# LcsNodes-Building-Block-Extension-Logic.net
KiCad netlist of a schematic drawn in EasyEDA
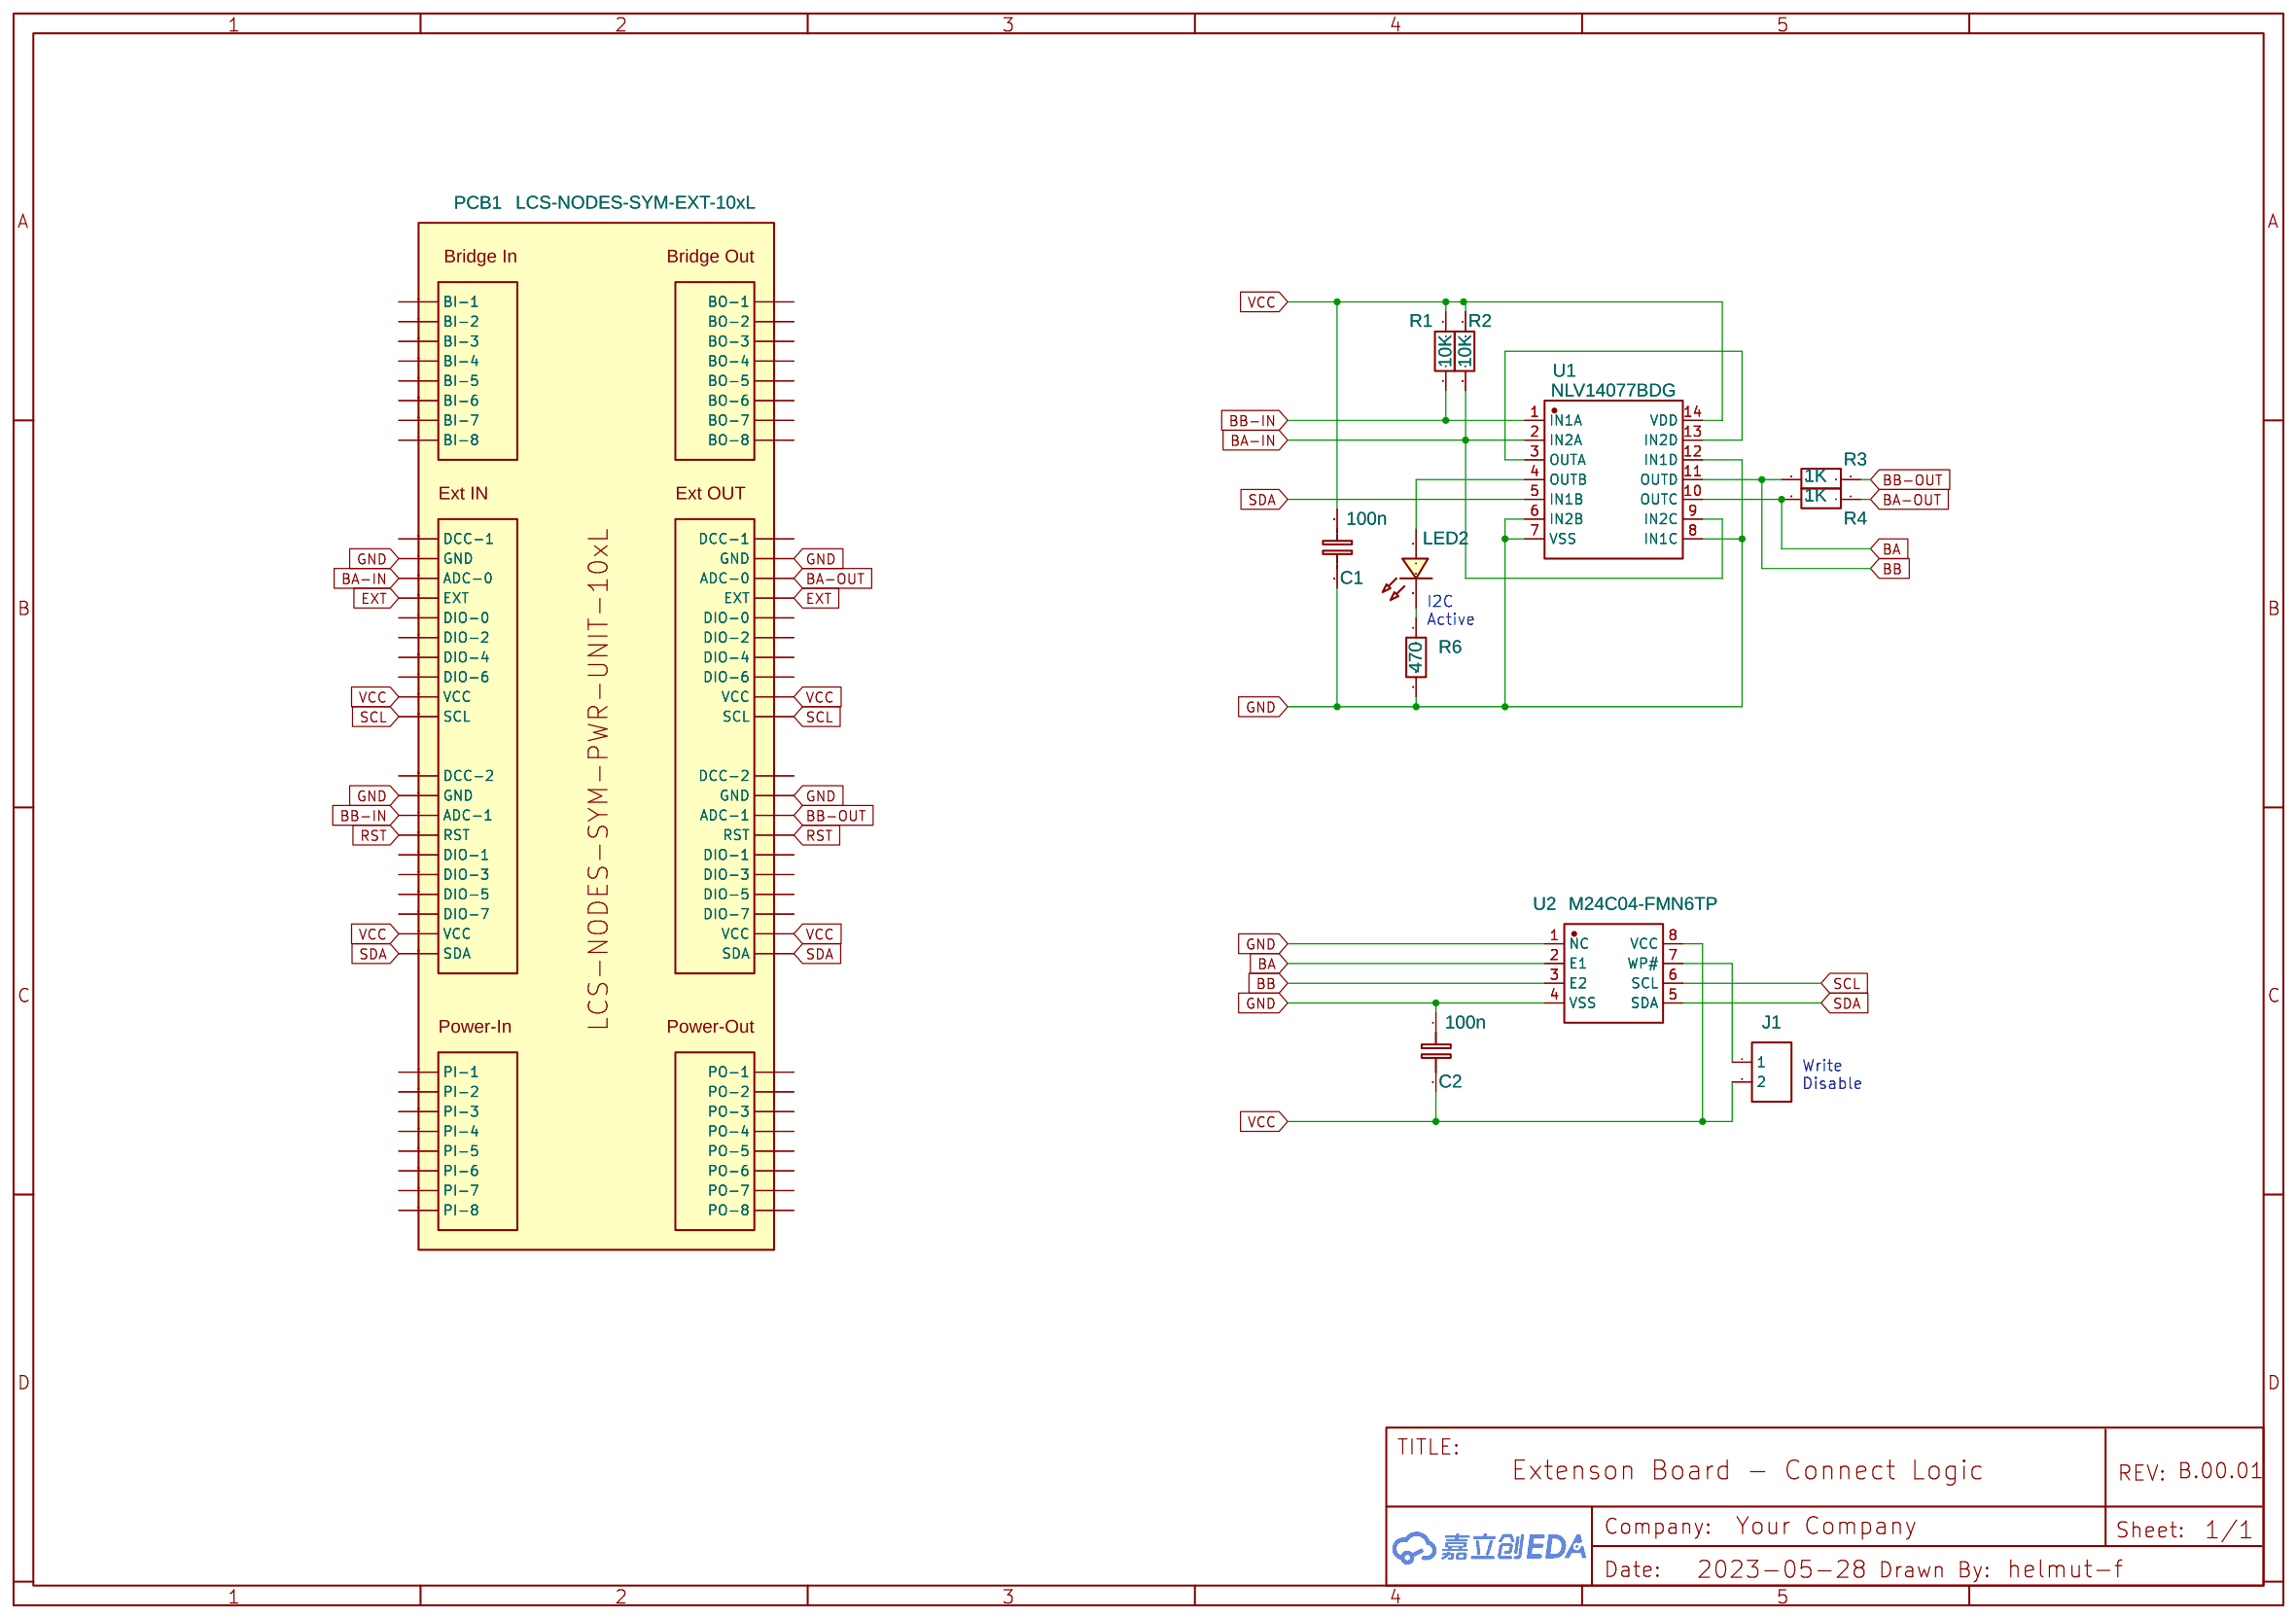
[diagram p0: schematic sheet]

(export (version "E")
  (design (tool "Eeschema 10.0.6"))
  (components
    (comp (ref "C1") (value "100n") (libsource (lib "") (part "C_0603_EU_1")))
    (comp (ref "C2") (value "100n") (libsource (lib "") (part "C_0603_EU")))
    (comp (ref "J1") (value "HDR-M-2.54_1x2") (libsource (lib "") (part "HDR-M-2.54_1x2")))
    (comp (ref "LED2")
      (value "LED-0805_G")
      (fields (field (name "Manufacturer Part") "NCD0805G1") (field (name "Manufacturer") "国星光电"))
      (libsource (lib "") (part "LED-0805_G"))
    )
    (comp (ref "PCB1") (value "LCS-NODES-SYM-EXT-10xL") (libsource (lib "") (part "LCS-NODES-SYM-EXT-10X8")))
    (comp (ref "R1") (value "10K") (libsource (lib "") (part "R_AXIAL-0.3_EU")))
    (comp (ref "R2") (value "10K") (libsource (lib "") (part "R_AXIAL-0.3_EU")))
    (comp (ref "R3") (value "1K") (libsource (lib "") (part "R_AXIAL-0.3_EU_1")))
    (comp (ref "R4") (value "1K") (libsource (lib "") (part "R_AXIAL-0.3_EU_1")))
    (comp (ref "R6") (value "470") (libsource (lib "") (part "R_0805_EU")))
    (comp (ref "U1")
      (value "NLV14077BDG")
      (fields (field (name "Manufacturer") "onsemi(安森美)"))
      (libsource (lib "") (part "NLV14077BDG"))
    )
    (comp (ref "U2")
      (value "M24C04-FMN6TP")
      (fields (field (name "Manufacturer") "ST(意法半导体)"))
      (libsource (lib "") (part "M24C04-FMN6TP"))
    )
  )
  (nets
    (net (code "1") (name "BA") (class "Default")
      (node (ref "R4") (pin "2") (pinfunction "2_2") (pintype "unspecified"))
      (node (ref "U1") (pin "10") (pinfunction "OUTC_10") (pintype "unspecified"))
      (node (ref "U2") (pin "2") (pinfunction "E1_2") (pintype "unspecified"))
    )
    (net (code "2") (name "BA-IN") (class "Default")
      (node (ref "PCB1") (pin "22") (pinfunction "ADC-0_22") (pintype "unspecified"))
      (node (ref "R2") (pin "2") (pinfunction "2_2") (pintype "unspecified"))
      (node (ref "U1") (pin "2") (pinfunction "IN2A_2") (pintype "unspecified"))
      (node (ref "U1") (pin "9") (pinfunction "IN2C_9") (pintype "unspecified"))
    )
    (net (code "3") (name "BA-OUT") (class "Default")
      (node (ref "PCB1") (pin "62") (pinfunction "ADC-0_62") (pintype "unspecified"))
      (node (ref "R4") (pin "1") (pinfunction "1_1") (pintype "unspecified"))
    )
    (net (code "4") (name "BB") (class "Default")
      (node (ref "R3") (pin "2") (pinfunction "2_2") (pintype "unspecified"))
      (node (ref "U1") (pin "11") (pinfunction "OUTD_11") (pintype "unspecified"))
      (node (ref "U2") (pin "3") (pinfunction "E2_3") (pintype "unspecified"))
    )
    (net (code "5") (name "BB-IN") (class "Default")
      (node (ref "PCB1") (pin "32") (pinfunction "ADC-1_32") (pintype "unspecified"))
      (node (ref "R1") (pin "2") (pinfunction "2_2") (pintype "unspecified"))
      (node (ref "U1") (pin "1") (pinfunction "IN1A_1") (pintype "unspecified"))
    )
    (net (code "6") (name "BB-OUT") (class "Default")
      (node (ref "PCB1") (pin "72") (pinfunction "ADC-1_72") (pintype "unspecified"))
      (node (ref "R3") (pin "1") (pinfunction "1_1") (pintype "unspecified"))
    )
    (net (code "7") (name "EXT") (class "Default")
      (node (ref "PCB1") (pin "23") (pinfunction "EXT_23") (pintype "unspecified"))
      (node (ref "PCB1") (pin "63") (pinfunction "EXT_63") (pintype "unspecified"))
    )
    (net (code "8") (name "GND") (class "Default")
      (node (ref "C1") (pin "2") (pinfunction "2_2") (pintype "unspecified"))
      (node (ref "C2") (pin "1") (pinfunction "1_1") (pintype "unspecified"))
      (node (ref "PCB1") (pin "21") (pinfunction "GND_21") (pintype "unspecified"))
      (node (ref "PCB1") (pin "31") (pinfunction "GND_31") (pintype "unspecified"))
      (node (ref "PCB1") (pin "61") (pinfunction "GND_61") (pintype "unspecified"))
      (node (ref "PCB1") (pin "71") (pinfunction "GND_71") (pintype "unspecified"))
      (node (ref "R6") (pin "2") (pinfunction "2_2") (pintype "unspecified"))
      (node (ref "U1") (pin "12") (pinfunction "IN1D_12") (pintype "unspecified"))
      (node (ref "U1") (pin "6") (pinfunction "IN2B_6") (pintype "unspecified"))
      (node (ref "U1") (pin "7") (pinfunction "VSS_7") (pintype "unspecified"))
      (node (ref "U1") (pin "8") (pinfunction "IN1C_8") (pintype "unspecified"))
      (node (ref "U2") (pin "1") (pinfunction "NC_1") (pintype "unspecified"))
      (node (ref "U2") (pin "4") (pinfunction "VSS_4") (pintype "unspecified"))
    )
    (net (code "9") (name "Net-(LED2-Pad2)") (class "Default")
      (node (ref "LED2") (pin "2") (pinfunction "2_2") (pintype "unspecified"))
      (node (ref "R6") (pin "1") (pinfunction "1_1") (pintype "unspecified"))
    )
    (net (code "10") (name "Net-(U1-IN2D)") (class "Default")
      (node (ref "U1") (pin "13") (pinfunction "IN2D_13") (pintype "unspecified"))
      (node (ref "U1") (pin "3") (pinfunction "OUTA_3") (pintype "unspecified"))
    )
    (net (code "11") (name "Net-(U1-OUTB)") (class "Default")
      (node (ref "LED2") (pin "1") (pinfunction "1_1") (pintype "unspecified"))
      (node (ref "U1") (pin "4") (pinfunction "OUTB_4") (pintype "unspecified"))
    )
    (net (code "12") (name "Net-(U2-WP#)") (class "Default")
      (node (ref "J1") (pin "1") (pinfunction "1_1") (pintype "unspecified"))
      (node (ref "U2") (pin "7") (pinfunction "WP#_7") (pintype "unspecified"))
    )
    (net (code "13") (name "RST") (class "Default")
      (node (ref "PCB1") (pin "33") (pinfunction "RST_33") (pintype "unspecified"))
      (node (ref "PCB1") (pin "73") (pinfunction "RST_73") (pintype "unspecified"))
    )
    (net (code "14") (name "SCL") (class "Default")
      (node (ref "PCB1") (pin "29") (pinfunction "SCL_29") (pintype "unspecified"))
      (node (ref "PCB1") (pin "69") (pinfunction "SCL_69") (pintype "unspecified"))
      (node (ref "U2") (pin "6") (pinfunction "SCL_6") (pintype "unspecified"))
    )
    (net (code "15") (name "SDA") (class "Default")
      (node (ref "PCB1") (pin "39") (pinfunction "SDA_39") (pintype "unspecified"))
      (node (ref "PCB1") (pin "79") (pinfunction "SDA_79") (pintype "unspecified"))
      (node (ref "U1") (pin "5") (pinfunction "IN1B_5") (pintype "unspecified"))
      (node (ref "U2") (pin "5") (pinfunction "SDA_5") (pintype "unspecified"))
    )
    (net (code "16") (name "VCC") (class "Default")
      (node (ref "C1") (pin "1") (pinfunction "1_1") (pintype "unspecified"))
      (node (ref "C2") (pin "2") (pinfunction "2_2") (pintype "unspecified"))
      (node (ref "J1") (pin "2") (pinfunction "2_2") (pintype "unspecified"))
      (node (ref "PCB1") (pin "28") (pinfunction "VCC_28") (pintype "unspecified"))
      (node (ref "PCB1") (pin "38") (pinfunction "VCC_38") (pintype "unspecified"))
      (node (ref "PCB1") (pin "68") (pinfunction "VCC_68") (pintype "unspecified"))
      (node (ref "PCB1") (pin "78") (pinfunction "VCC_78") (pintype "unspecified"))
      (node (ref "R1") (pin "1") (pinfunction "1_1") (pintype "unspecified"))
      (node (ref "R2") (pin "1") (pinfunction "1_1") (pintype "unspecified"))
      (node (ref "U1") (pin "14") (pinfunction "VDD_14") (pintype "unspecified"))
      (node (ref "U2") (pin "8") (pinfunction "VCC_8") (pintype "unspecified"))
    )
    (net (code "17") (name "unconnected-(PCB1-BI-1-Pad10)") (class "Default")
      (node (ref "PCB1") (pin "10") (pinfunction "BI-1_10") (pintype "unspecified"))
    )
    (net (code "18") (name "unconnected-(PCB1-BI-2-Pad11)") (class "Default")
      (node (ref "PCB1") (pin "11") (pinfunction "BI-2_11") (pintype "unspecified"))
    )
    (net (code "19") (name "unconnected-(PCB1-BI-3-Pad12)") (class "Default")
      (node (ref "PCB1") (pin "12") (pinfunction "BI-3_12") (pintype "unspecified"))
    )
    (net (code "20") (name "unconnected-(PCB1-BI-4-Pad13)") (class "Default")
      (node (ref "PCB1") (pin "13") (pinfunction "BI-4_13") (pintype "unspecified"))
    )
    (net (code "21") (name "unconnected-(PCB1-BI-5-Pad14)") (class "Default")
      (node (ref "PCB1") (pin "14") (pinfunction "BI-5_14") (pintype "unspecified"))
    )
    (net (code "22") (name "unconnected-(PCB1-BI-6-Pad15)") (class "Default")
      (node (ref "PCB1") (pin "15") (pinfunction "BI-6_15") (pintype "unspecified"))
    )
    (net (code "23") (name "unconnected-(PCB1-BI-7-Pad16)") (class "Default")
      (node (ref "PCB1") (pin "16") (pinfunction "BI-7_16") (pintype "unspecified"))
    )
    (net (code "24") (name "unconnected-(PCB1-BI-8-Pad17)") (class "Default")
      (node (ref "PCB1") (pin "17") (pinfunction "BI-8_17") (pintype "unspecified"))
    )
    (net (code "25") (name "unconnected-(PCB1-BO-1-Pad50)") (class "Default")
      (node (ref "PCB1") (pin "50") (pinfunction "BO-1_50") (pintype "unspecified"))
    )
    (net (code "26") (name "unconnected-(PCB1-BO-2-Pad51)") (class "Default")
      (node (ref "PCB1") (pin "51") (pinfunction "BO-2_51") (pintype "unspecified"))
    )
    (net (code "27") (name "unconnected-(PCB1-BO-3-Pad52)") (class "Default")
      (node (ref "PCB1") (pin "52") (pinfunction "BO-3_52") (pintype "unspecified"))
    )
    (net (code "28") (name "unconnected-(PCB1-BO-4-Pad53)") (class "Default")
      (node (ref "PCB1") (pin "53") (pinfunction "BO-4_53") (pintype "unspecified"))
    )
    (net (code "29") (name "unconnected-(PCB1-BO-5-Pad54)") (class "Default")
      (node (ref "PCB1") (pin "54") (pinfunction "BO-5_54") (pintype "unspecified"))
    )
    (net (code "30") (name "unconnected-(PCB1-BO-6-Pad55)") (class "Default")
      (node (ref "PCB1") (pin "55") (pinfunction "BO-6_55") (pintype "unspecified"))
    )
    (net (code "31") (name "unconnected-(PCB1-BO-7-Pad56)") (class "Default")
      (node (ref "PCB1") (pin "56") (pinfunction "BO-7_56") (pintype "unspecified"))
    )
    (net (code "32") (name "unconnected-(PCB1-BO-8-Pad57)") (class "Default")
      (node (ref "PCB1") (pin "57") (pinfunction "BO-8_57") (pintype "unspecified"))
    )
    (net (code "33") (name "unconnected-(PCB1-DCC-1-Pad20)") (class "Default")
      (node (ref "PCB1") (pin "20") (pinfunction "DCC-1_20") (pintype "unspecified"))
    )
    (net (code "34") (name "unconnected-(PCB1-DCC-1-Pad60)") (class "Default")
      (node (ref "PCB1") (pin "60") (pinfunction "DCC-1_60") (pintype "unspecified"))
    )
    (net (code "35") (name "unconnected-(PCB1-DCC-2-Pad30)") (class "Default")
      (node (ref "PCB1") (pin "30") (pinfunction "DCC-2_30") (pintype "unspecified"))
    )
    (net (code "36") (name "unconnected-(PCB1-DCC-2-Pad70)") (class "Default")
      (node (ref "PCB1") (pin "70") (pinfunction "DCC-2_70") (pintype "unspecified"))
    )
    (net (code "37") (name "unconnected-(PCB1-DIO-0-Pad24)") (class "Default")
      (node (ref "PCB1") (pin "24") (pinfunction "DIO-0_24") (pintype "unspecified"))
    )
    (net (code "38") (name "unconnected-(PCB1-DIO-0-Pad64)") (class "Default")
      (node (ref "PCB1") (pin "64") (pinfunction "DIO-0_64") (pintype "unspecified"))
    )
    (net (code "39") (name "unconnected-(PCB1-DIO-1-Pad34)") (class "Default")
      (node (ref "PCB1") (pin "34") (pinfunction "DIO-1_34") (pintype "unspecified"))
    )
    (net (code "40") (name "unconnected-(PCB1-DIO-1-Pad74)") (class "Default")
      (node (ref "PCB1") (pin "74") (pinfunction "DIO-1_74") (pintype "unspecified"))
    )
    (net (code "41") (name "unconnected-(PCB1-DIO-2-Pad25)") (class "Default")
      (node (ref "PCB1") (pin "25") (pinfunction "DIO-2_25") (pintype "unspecified"))
    )
    (net (code "42") (name "unconnected-(PCB1-DIO-2-Pad65)") (class "Default")
      (node (ref "PCB1") (pin "65") (pinfunction "DIO-2_65") (pintype "unspecified"))
    )
    (net (code "43") (name "unconnected-(PCB1-DIO-3-Pad35)") (class "Default")
      (node (ref "PCB1") (pin "35") (pinfunction "DIO-3_35") (pintype "unspecified"))
    )
    (net (code "44") (name "unconnected-(PCB1-DIO-3-Pad75)") (class "Default")
      (node (ref "PCB1") (pin "75") (pinfunction "DIO-3_75") (pintype "unspecified"))
    )
    (net (code "45") (name "unconnected-(PCB1-DIO-4-Pad26)") (class "Default")
      (node (ref "PCB1") (pin "26") (pinfunction "DIO-4_26") (pintype "unspecified"))
    )
    (net (code "46") (name "unconnected-(PCB1-DIO-4-Pad66)") (class "Default")
      (node (ref "PCB1") (pin "66") (pinfunction "DIO-4_66") (pintype "unspecified"))
    )
    (net (code "47") (name "unconnected-(PCB1-DIO-5-Pad36)") (class "Default")
      (node (ref "PCB1") (pin "36") (pinfunction "DIO-5_36") (pintype "unspecified"))
    )
    (net (code "48") (name "unconnected-(PCB1-DIO-5-Pad76)") (class "Default")
      (node (ref "PCB1") (pin "76") (pinfunction "DIO-5_76") (pintype "unspecified"))
    )
    (net (code "49") (name "unconnected-(PCB1-DIO-6-Pad27)") (class "Default")
      (node (ref "PCB1") (pin "27") (pinfunction "DIO-6_27") (pintype "unspecified"))
    )
    (net (code "50") (name "unconnected-(PCB1-DIO-6-Pad67)") (class "Default")
      (node (ref "PCB1") (pin "67") (pinfunction "DIO-6_67") (pintype "unspecified"))
    )
    (net (code "51") (name "unconnected-(PCB1-DIO-7-Pad37)") (class "Default")
      (node (ref "PCB1") (pin "37") (pinfunction "DIO-7_37") (pintype "unspecified"))
    )
    (net (code "52") (name "unconnected-(PCB1-DIO-7-Pad77)") (class "Default")
      (node (ref "PCB1") (pin "77") (pinfunction "DIO-7_77") (pintype "unspecified"))
    )
    (net (code "53") (name "unconnected-(PCB1-PI-1-Pad40)") (class "Default")
      (node (ref "PCB1") (pin "40") (pinfunction "PI-1_40") (pintype "unspecified"))
    )
    (net (code "54") (name "unconnected-(PCB1-PI-2-Pad41)") (class "Default")
      (node (ref "PCB1") (pin "41") (pinfunction "PI-2_41") (pintype "unspecified"))
    )
    (net (code "55") (name "unconnected-(PCB1-PI-3-Pad42)") (class "Default")
      (node (ref "PCB1") (pin "42") (pinfunction "PI-3_42") (pintype "unspecified"))
    )
    (net (code "56") (name "unconnected-(PCB1-PI-4-Pad43)") (class "Default")
      (node (ref "PCB1") (pin "43") (pinfunction "PI-4_43") (pintype "unspecified"))
    )
    (net (code "57") (name "unconnected-(PCB1-PI-5-Pad44)") (class "Default")
      (node (ref "PCB1") (pin "44") (pinfunction "PI-5_44") (pintype "unspecified"))
    )
    (net (code "58") (name "unconnected-(PCB1-PI-6-Pad45)") (class "Default")
      (node (ref "PCB1") (pin "45") (pinfunction "PI-6_45") (pintype "unspecified"))
    )
    (net (code "59") (name "unconnected-(PCB1-PI-7-Pad46)") (class "Default")
      (node (ref "PCB1") (pin "46") (pinfunction "PI-7_46") (pintype "unspecified"))
    )
    (net (code "60") (name "unconnected-(PCB1-PI-8-Pad47)") (class "Default")
      (node (ref "PCB1") (pin "47") (pinfunction "PI-8_47") (pintype "unspecified"))
    )
    (net (code "61") (name "unconnected-(PCB1-PO-1-Pad80)") (class "Default")
      (node (ref "PCB1") (pin "80") (pinfunction "PO-1_80") (pintype "unspecified"))
    )
    (net (code "62") (name "unconnected-(PCB1-PO-2-Pad81)") (class "Default")
      (node (ref "PCB1") (pin "81") (pinfunction "PO-2_81") (pintype "unspecified"))
    )
    (net (code "63") (name "unconnected-(PCB1-PO-3-Pad82)") (class "Default")
      (node (ref "PCB1") (pin "82") (pinfunction "PO-3_82") (pintype "unspecified"))
    )
    (net (code "64") (name "unconnected-(PCB1-PO-4-Pad83)") (class "Default")
      (node (ref "PCB1") (pin "83") (pinfunction "PO-4_83") (pintype "unspecified"))
    )
    (net (code "65") (name "unconnected-(PCB1-PO-5-Pad84)") (class "Default")
      (node (ref "PCB1") (pin "84") (pinfunction "PO-5_84") (pintype "unspecified"))
    )
    (net (code "66") (name "unconnected-(PCB1-PO-6-Pad85)") (class "Default")
      (node (ref "PCB1") (pin "85") (pinfunction "PO-6_85") (pintype "unspecified"))
    )
    (net (code "67") (name "unconnected-(PCB1-PO-7-Pad86)") (class "Default")
      (node (ref "PCB1") (pin "86") (pinfunction "PO-7_86") (pintype "unspecified"))
    )
    (net (code "68") (name "unconnected-(PCB1-PO-8-Pad87)") (class "Default")
      (node (ref "PCB1") (pin "87") (pinfunction "PO-8_87") (pintype "unspecified"))
    )
  )
)
